# Display.net
KiCad netlist of a schematic drawn in Altium Designer
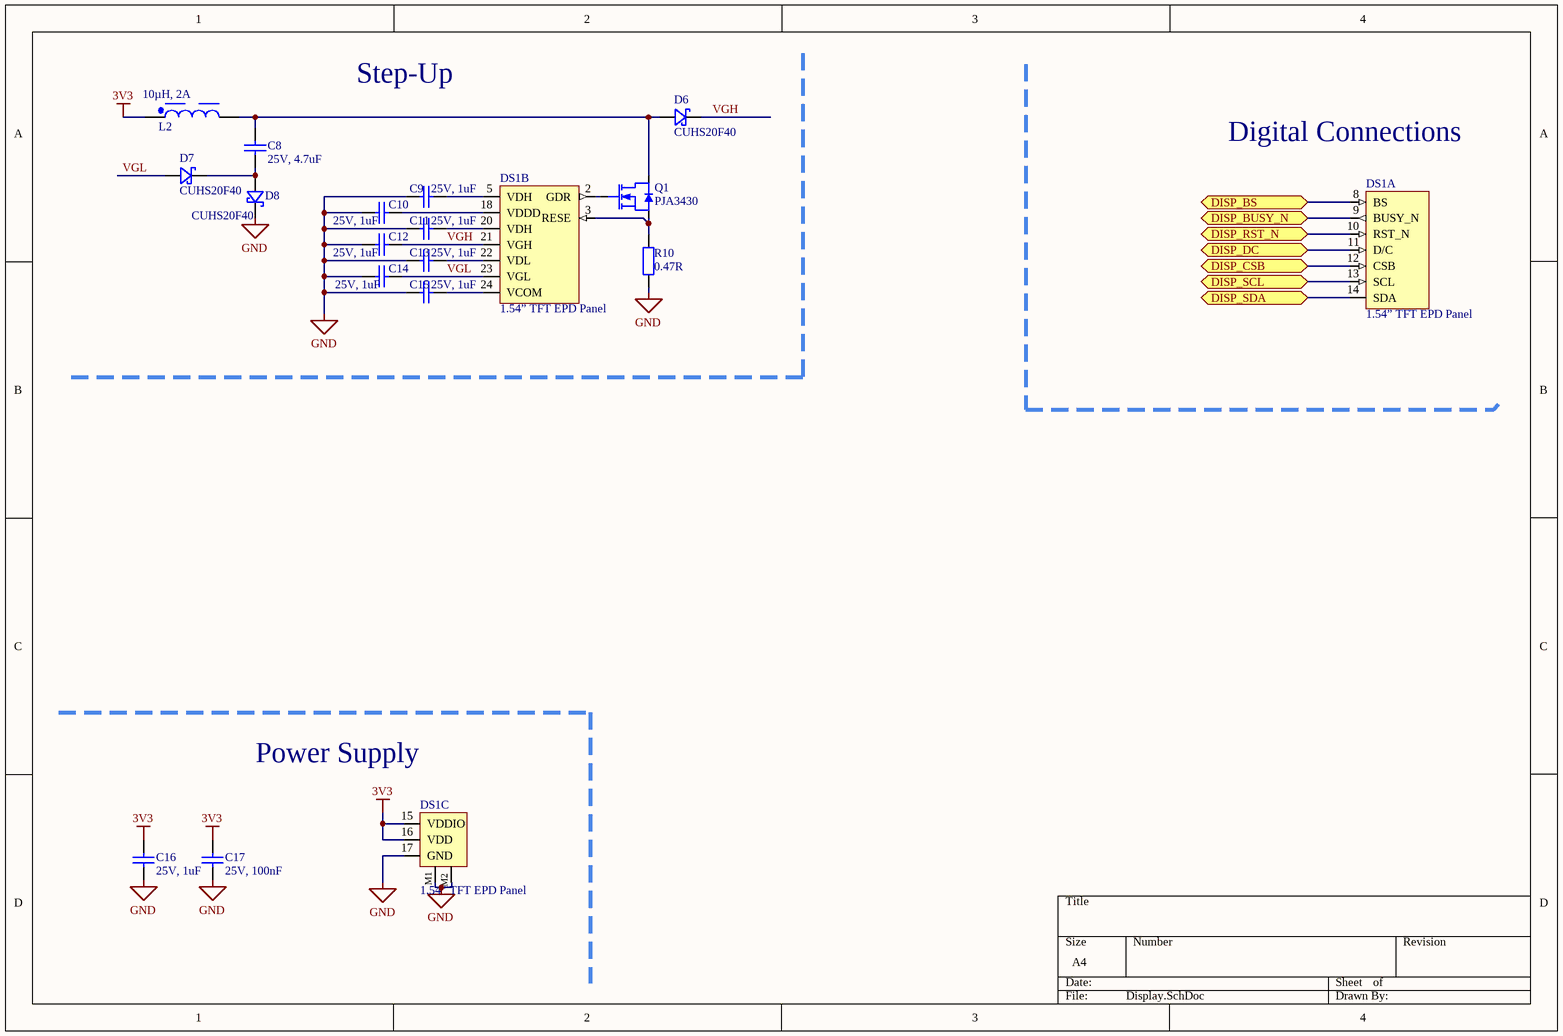
[diagram p0: Display.SchDoc]

(export (version "E")
  (design (tool "Eeschema 10.0.6"))
  (components
    (comp (ref "C8")
      (value "25V, 4.7uF")
      (footprint "0805_2x1.25x1.25mm_Reflow Soldering")
      (description "WCAP-CSGP Ceramic Capacitors, 0805, X5R, 25V, 4.7uF")
      (fields (field (name "PART NUMBER") "885012107018") (field (name "PUBLISHER") "Wurth Elektronik"))
      (libsource (lib "ALTIUM-WCAP-CSGP-0603-rev17b") (part "885012107018"))
    )
    (comp (ref "C9")
      (value "25V, 1uF")
      (footprint "0603_1.6x0.8x0.8mm_Reflow Soldering")
      (description "WCAP-CSGP Ceramic Capacitors, 0603, X5R, 25V, 1uF")
      (fields (field (name "PART NUMBER") "885012106022") (field (name "PUBLISHER") "Wurth Elektronik"))
      (libsource (lib "ALTIUM-WCAP-CSGP-0603-rev17b") (part "885012106022"))
    )
    (comp (ref "C10")
      (value "25V, 1uF")
      (footprint "0603_1.6x0.8x0.8mm_Reflow Soldering")
      (description "WCAP-CSGP Ceramic Capacitors, 0603, X5R, 25V, 1uF")
      (fields (field (name "PART NUMBER") "885012106022") (field (name "PUBLISHER") "Wurth Elektronik"))
      (libsource (lib "ALTIUM-WCAP-CSGP-0603-rev17b") (part "885012106022"))
    )
    (comp (ref "C11")
      (value "25V, 1uF")
      (footprint "0603_1.6x0.8x0.8mm_Reflow Soldering")
      (description "WCAP-CSGP Ceramic Capacitors, 0603, X5R, 25V, 1uF")
      (fields (field (name "PART NUMBER") "885012106022") (field (name "PUBLISHER") "Wurth Elektronik"))
      (libsource (lib "ALTIUM-WCAP-CSGP-0603-rev17b") (part "885012106022"))
    )
    (comp (ref "C12")
      (value "25V, 1uF")
      (footprint "0603_1.6x0.8x0.8mm_Reflow Soldering")
      (description "WCAP-CSGP Ceramic Capacitors, 0603, X5R, 25V, 1uF")
      (fields (field (name "PART NUMBER") "885012106022") (field (name "PUBLISHER") "Wurth Elektronik"))
      (libsource (lib "ALTIUM-WCAP-CSGP-0603-rev17b") (part "885012106022"))
    )
    (comp (ref "C13")
      (value "25V, 1uF")
      (footprint "0603_1.6x0.8x0.8mm_Reflow Soldering")
      (description "WCAP-CSGP Ceramic Capacitors, 0603, X5R, 25V, 1uF")
      (fields (field (name "PART NUMBER") "885012106022") (field (name "PUBLISHER") "Wurth Elektronik"))
      (libsource (lib "ALTIUM-WCAP-CSGP-0603-rev17b") (part "885012106022"))
    )
    (comp (ref "C14")
      (value "25V, 1uF")
      (footprint "0603_1.6x0.8x0.8mm_Reflow Soldering")
      (description "WCAP-CSGP Ceramic Capacitors, 0603, X5R, 25V, 1uF")
      (fields (field (name "PART NUMBER") "885012106022") (field (name "PUBLISHER") "Wurth Elektronik"))
      (libsource (lib "ALTIUM-WCAP-CSGP-0603-rev17b") (part "885012106022"))
    )
    (comp (ref "C15")
      (value "25V, 1uF")
      (footprint "0603_1.6x0.8x0.8mm_Reflow Soldering")
      (description "WCAP-CSGP Ceramic Capacitors, 0603, X5R, 25V, 1uF")
      (fields (field (name "PART NUMBER") "885012106022") (field (name "PUBLISHER") "Wurth Elektronik"))
      (libsource (lib "ALTIUM-WCAP-CSGP-0603-rev17b") (part "885012106022"))
    )
    (comp (ref "C16")
      (value "25V, 1uF")
      (footprint "0603_1.6x0.8x0.8mm_Reflow Soldering")
      (description "WCAP-CSGP Ceramic Capacitors, 0603, X5R, 25V, 1uF")
      (fields (field (name "PART NUMBER") "885012106022") (field (name "PUBLISHER") "Wurth Elektronik"))
      (libsource (lib "ALTIUM-WCAP-CSGP-0603-rev17b") (part "885012106022"))
    )
    (comp (ref "C17")
      (value "25V, 100nF")
      (footprint "0402_1x0.5x0.5mm")
      (description "WCAP-CSGP Ceramic Capacitors, 0402, X5R, 25V, 100nF")
      (fields (field (name "PART NUMBER") "885012105018") (field (name "PUBLISHER") "Wurth Elektronik"))
      (libsource (lib "ALTIUM-WCAP-CSGP-0603-rev17b") (part "885012105018"))
    )
    (comp (ref "D6")
      (value "CUHS20F40")
      (footprint "Topshiba US2H")
      (description "Schottky Barrier Diode Silicon Epitaxia")
      (libsource (lib "Oblak Library") (part "CUHS20F40"))
    )
    (comp (ref "D7")
      (value "CUHS20F40")
      (footprint "Topshiba US2H")
      (description "Schottky Barrier Diode Silicon Epitaxia")
      (libsource (lib "Oblak Library") (part "CUHS20F40"))
    )
    (comp (ref "D8")
      (value "CUHS20F40")
      (footprint "Topshiba US2H")
      (description "Schottky Barrier Diode Silicon Epitaxia")
      (libsource (lib "Oblak Library") (part "CUHS20F40"))
    )
    (comp (ref "DS1")
      (value "1.54” TFT EPD Panel")
      (footprint "687324124422")
      (description "Wurth 687124183622 connector for horizontal,\r\nWurth 687324124422 for vertical")
      (libsource (lib "Oblak Library") (part "E2154CS0C1"))
    )
    (comp (ref "L2")
      (value "10µH, 2A")
      (footprint "WE-TPC_8020")
      (description "WE-TPC SMT Tiny Power Inductor, 8020, 10µH, 2A, 94mΩ")
      (fields
        (field (name "MANUFACTURER PART NUMBER") "7440700100")
        (field (name "MANUFACTURER") "Wurth Elektronik")
      )
      (libsource (lib "WE-TPC (rev22c)") (part "7440700100"))
    )
    (comp (ref "Q1")
      (value "PJA3430")
      (footprint "SOT23")
      (description "20V/2A N-Channel Enhancment Mode MOSFET")
      (libsource (lib "Oblak Library") (part "PJA3430_R1_00001"))
    )
    (comp (ref "R10")
      (value "0.47R")
      (footprint "RES0805_1")
      (fields (field (name "Comment") "Res2-smd"))
      (libsource (lib "VolkD3D") (part "Res2-smd"))
    )
  )
  (nets
    (net (code "1") (name "/DISP_BS") (class "Default")
      (node (ref "DS1") (pin "8") (pinfunction "BS_8") (pintype "input"))
    )
    (net (code "2") (name "/DISP_BUSY_N") (class "Default")
      (node (ref "DS1") (pin "9") (pinfunction "BUSY_N_9") (pintype "output"))
    )
    (net (code "3") (name "/DISP_CSB") (class "Default")
      (node (ref "DS1") (pin "12") (pinfunction "CSB_12") (pintype "input"))
    )
    (net (code "4") (name "/DISP_DC") (class "Default")
      (node (ref "DS1") (pin "11") (pinfunction "D/C_11") (pintype "input"))
    )
    (net (code "5") (name "/DISP_RST_N") (class "Default")
      (node (ref "DS1") (pin "10") (pinfunction "RST_N_10") (pintype "input"))
    )
    (net (code "6") (name "/DISP_SCL") (class "Default")
      (node (ref "DS1") (pin "13") (pinfunction "SCL_13") (pintype "input"))
    )
    (net (code "7") (name "/DISP_SDA") (class "Default")
      (node (ref "DS1") (pin "14") (pinfunction "SDA_14") (pintype "bidirectional"))
    )
    (net (code "8") (name "/VGH") (class "Default")
      (node (ref "C12") (pin "2") (pinfunction "2_2") (pintype "passive"))
      (node (ref "D6") (pin "1") (pinfunction "K_1") (pintype "passive"))
      (node (ref "DS1") (pin "21") (pinfunction "VGH_21") (pintype "passive"))
    )
    (net (code "9") (name "/VGL") (class "Default")
      (node (ref "C14") (pin "2") (pinfunction "2_2") (pintype "passive"))
      (node (ref "D7") (pin "2") (pinfunction "A_2") (pintype "passive"))
      (node (ref "DS1") (pin "23") (pinfunction "VGL_23") (pintype "passive"))
    )
    (net (code "10") (name "3V3") (class "Default")
      (node (ref "C16") (pin "2") (pinfunction "2_2") (pintype "passive"))
      (node (ref "C17") (pin "2") (pinfunction "2_2") (pintype "passive"))
      (node (ref "DS1") (pin "15") (pinfunction "VDDIO_15") (pintype "power_in"))
      (node (ref "DS1") (pin "16") (pinfunction "VDD_16") (pintype "power_in"))
      (node (ref "L2") (pin "1") (pinfunction "1_1") (pintype "passive"))
    )
    (net (code "11") (name "GND") (class "Default")
      (node (ref "C10") (pin "1") (pinfunction "1_1") (pintype "passive"))
      (node (ref "C11") (pin "1") (pinfunction "1_1") (pintype "passive"))
      (node (ref "C12") (pin "1") (pinfunction "1_1") (pintype "passive"))
      (node (ref "C13") (pin "1") (pinfunction "1_1") (pintype "passive"))
      (node (ref "C14") (pin "1") (pinfunction "1_1") (pintype "passive"))
      (node (ref "C15") (pin "1") (pinfunction "1_1") (pintype "passive"))
      (node (ref "C16") (pin "1") (pinfunction "1_1") (pintype "passive"))
      (node (ref "C17") (pin "1") (pinfunction "1_1") (pintype "passive"))
      (node (ref "C9") (pin "1") (pinfunction "1_1") (pintype "passive"))
      (node (ref "D8") (pin "1") (pinfunction "K_1") (pintype "passive"))
      (node (ref "DS1") (pin "17") (pinfunction "GND_17") (pintype "power_in"))
      (node (ref "DS1") (pin "M1") (pinfunction "M1_M1") (pintype "passive"))
      (node (ref "DS1") (pin "M2") (pinfunction "M2_M2") (pintype "passive"))
      (node (ref "R10") (pin "1") (pinfunction "1_1") (pintype "passive"))
    )
    (net (code "12") (name "Net-(C9-Pad2)") (class "Default")
      (node (ref "C9") (pin "2") (pinfunction "2_2") (pintype "passive"))
      (node (ref "DS1") (pin "5") (pinfunction "VDH_5") (pintype "passive"))
    )
    (net (code "13") (name "Net-(C11-Pad2)") (class "Default")
      (node (ref "C11") (pin "2") (pinfunction "2_2") (pintype "passive"))
      (node (ref "DS1") (pin "20") (pinfunction "VDH_20") (pintype "passive"))
    )
    (net (code "14") (name "Net-(D6-A)") (class "Default")
      (node (ref "C8") (pin "2") (pinfunction "2_2") (pintype "passive"))
      (node (ref "D6") (pin "2") (pinfunction "A_2") (pintype "passive"))
      (node (ref "L2") (pin "2") (pinfunction "2_2") (pintype "passive"))
      (node (ref "Q1") (pin "3") (pinfunction "D_3") (pintype "passive"))
    )
    (net (code "15") (name "Net-(D7-K)") (class "Default")
      (node (ref "C8") (pin "1") (pinfunction "1_1") (pintype "passive"))
      (node (ref "D7") (pin "1") (pinfunction "K_1") (pintype "passive"))
      (node (ref "D8") (pin "2") (pinfunction "A_2") (pintype "passive"))
    )
    (net (code "16") (name "Net-(DS1B-GDR)") (class "Default")
      (node (ref "DS1") (pin "2") (pinfunction "GDR_2") (pintype "output"))
      (node (ref "Q1") (pin "1") (pinfunction "G_1") (pintype "passive"))
    )
    (net (code "17") (name "Net-(DS1B-RESE)") (class "Default")
      (node (ref "DS1") (pin "3") (pinfunction "RESE_3") (pintype "input"))
      (node (ref "Q1") (pin "2") (pinfunction "S_2") (pintype "passive"))
      (node (ref "R10") (pin "2") (pinfunction "2_2") (pintype "passive"))
    )
    (net (code "18") (name "Net-(DS1B-VCOM)") (class "Default")
      (node (ref "C15") (pin "2") (pinfunction "2_2") (pintype "passive"))
      (node (ref "DS1") (pin "24") (pinfunction "VCOM_24") (pintype "passive"))
    )
    (net (code "19") (name "Net-(DS1B-VDDD)") (class "Default")
      (node (ref "C10") (pin "2") (pinfunction "2_2") (pintype "passive"))
      (node (ref "DS1") (pin "18") (pinfunction "VDDD_18") (pintype "passive"))
    )
    (net (code "20") (name "Net-(DS1B-VDL)") (class "Default")
      (node (ref "C13") (pin "2") (pinfunction "2_2") (pintype "passive"))
      (node (ref "DS1") (pin "22") (pinfunction "VDL_22") (pintype "passive"))
    )
  )
)
